# USB_CP2102.net
KiCad netlist of a schematic drawn in Altium Designer
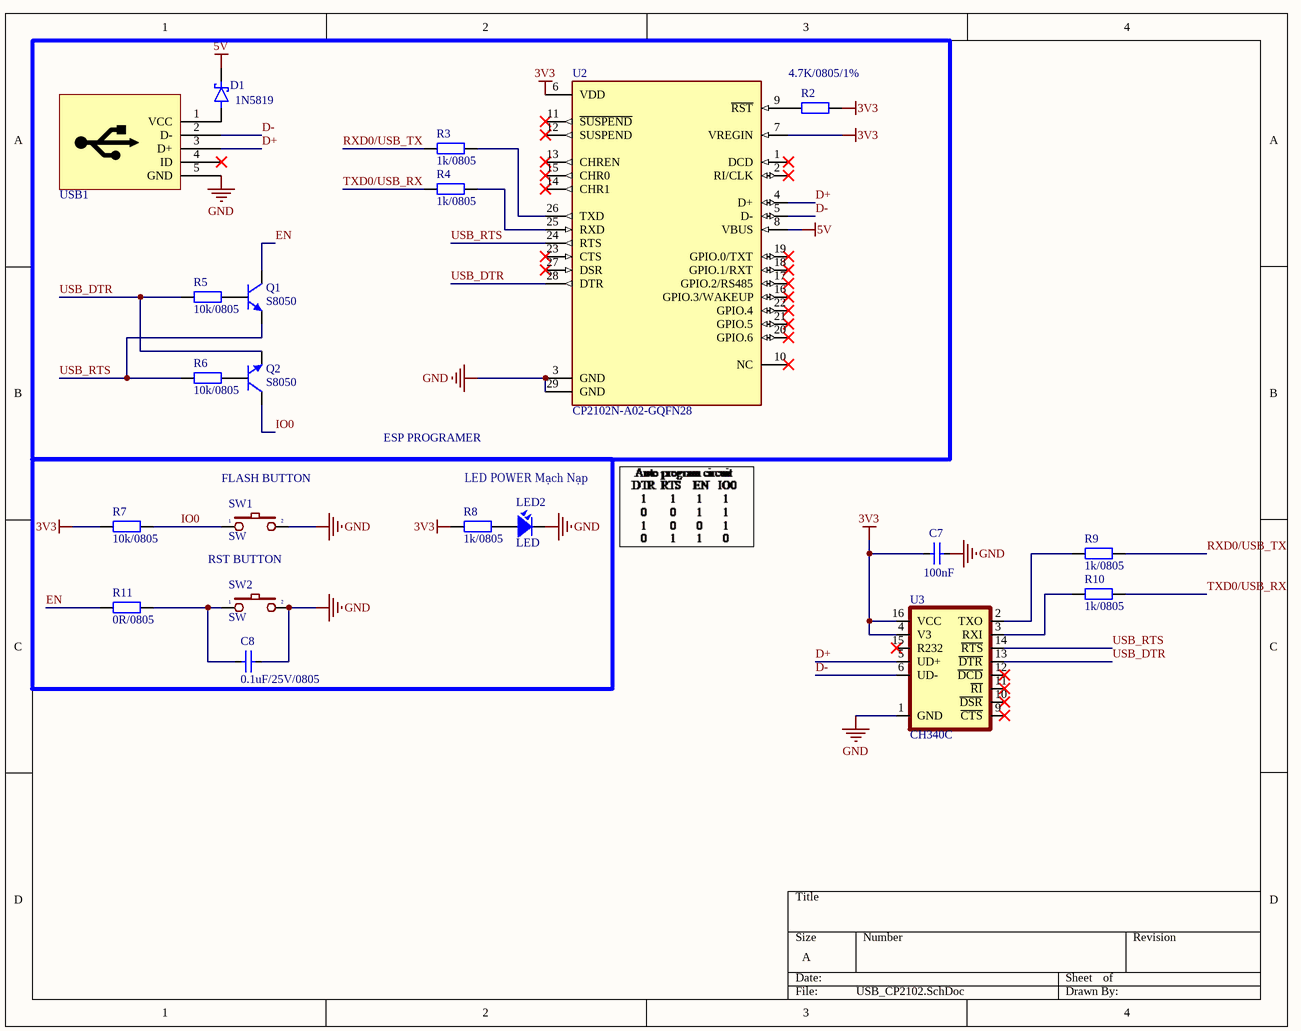
[diagram p0: USB_CP2102.SchDoc]

(export (version "E")
  (design (tool "Eeschema 10.0.6"))
  (components
    (comp (ref "C7")
      (value "100nF")
      (footprint "CAP_0402")
      (description "Capacitor")
      (fields (field (name "PUBLISHER") "Altium Limited"))
      (libsource (lib "My Library") (part "CapSMD"))
    )
    (comp (ref "C8")
      (value "0.1uF/25V/0805")
      (footprint "CAP_0805")
      (description "Capacitor")
      (fields (field (name "PUBLISHER") "Altium Limited"))
      (libsource (lib "My Library") (part "CapSMD"))
    )
    (comp (ref "D1")
      (value "1N5819")
      (footprint "SOD3715X145N")
      (description "Diode Schottky 40 V 1A Surface Mount SOD-123")
      (fields (field (name "MF") "Diodes Inc.") (field (name "MP") "1N5819HW-7-F"))
      (libsource (lib "1N5819HW-7-F") (part "1N5819HW-7-F"))
    )
    (comp (ref "LED2")
      (value "LED")
      (footprint "LED-0805-Green")
      (description "LED Single colour Green and Red")
      (libsource (lib "My Library") (part "LED"))
    )
    (comp (ref "Q1")
      (value "S8050")
      (footprint "SOT23")
      (description "NPN General")
      (fields (field (name "PUBLISHER") "Altium Limited"))
      (libsource (lib "My Library") (part "NPN"))
    )
    (comp (ref "Q2")
      (value "S8050")
      (footprint "SOT23")
      (description "NPN General")
      (fields (field (name "PUBLISHER") "Altium Limited"))
      (libsource (lib "My Library") (part "NPN"))
    )
    (comp (ref "R2")
      (value "4.7K/0805/1%")
      (footprint "RES-SMD-0805")
      (description "Resistor SMD")
      (fields
        (field (name "MANUFACTURER") "Generic Components")
        (field (name "PUBLISHER") "Altium Hobart Technology Centre")
      )
      (libsource (lib "My Library") (part "Resistor - SMD"))
    )
    (comp (ref "R3")
      (value "1k/0805")
      (footprint "RES-SMD-0805")
      (description "Resistor SMD")
      (fields
        (field (name "MANUFACTURER") "Generic Components")
        (field (name "PUBLISHER") "Altium Hobart Technology Centre")
      )
      (libsource (lib "My Library") (part "Resistor - SMD"))
    )
    (comp (ref "R4")
      (value "1k/0805")
      (footprint "RES-SMD-0805")
      (description "Resistor SMD")
      (fields
        (field (name "MANUFACTURER") "Generic Components")
        (field (name "PUBLISHER") "Altium Hobart Technology Centre")
      )
      (libsource (lib "My Library") (part "Resistor - SMD"))
    )
    (comp (ref "R5")
      (value "10k/0805")
      (footprint "RES-SMD-0805")
      (description "Resistor SMD")
      (fields
        (field (name "MANUFACTURER") "Generic Components")
        (field (name "PUBLISHER") "Altium Hobart Technology Centre")
      )
      (libsource (lib "My Library") (part "Resistor - SMD"))
    )
    (comp (ref "R6")
      (value "10k/0805")
      (footprint "RES-SMD-0805")
      (description "Resistor SMD")
      (fields
        (field (name "MANUFACTURER") "Generic Components")
        (field (name "PUBLISHER") "Altium Hobart Technology Centre")
      )
      (libsource (lib "My Library") (part "Resistor - SMD"))
    )
    (comp (ref "R7")
      (value "10k/0805")
      (footprint "RES-SMD-0805")
      (description "Resistor SMD")
      (fields
        (field (name "MANUFACTURER") "Generic Components")
        (field (name "PUBLISHER") "Altium Hobart Technology Centre")
      )
      (libsource (lib "My Library") (part "Resistor - SMD"))
    )
    (comp (ref "R8")
      (value "1k/0805")
      (footprint "RES-SMD-0805")
      (description "Resistor SMD")
      (fields
        (field (name "MANUFACTURER") "Generic Components")
        (field (name "PUBLISHER") "Altium Hobart Technology Centre")
      )
      (libsource (lib "My Library") (part "Resistor - SMD"))
    )
    (comp (ref "R9")
      (value "1k/0805")
      (footprint "RES-SMD-0805")
      (description "Resistor SMD")
      (fields
        (field (name "MANUFACTURER") "Generic Components")
        (field (name "PUBLISHER") "Altium Hobart Technology Centre")
      )
      (libsource (lib "My Library") (part "Resistor - SMD"))
    )
    (comp (ref "R10")
      (value "1k/0805")
      (footprint "RES-SMD-0805")
      (description "Resistor SMD")
      (fields
        (field (name "MANUFACTURER") "Generic Components")
        (field (name "PUBLISHER") "Altium Hobart Technology Centre")
      )
      (libsource (lib "My Library") (part "Resistor - SMD"))
    )
    (comp (ref "R11")
      (value "0R/0805")
      (footprint "RES-SMD-0805")
      (description "Resistor SMD")
      (fields
        (field (name "MANUFACTURER") "Generic Components")
        (field (name "PUBLISHER") "Altium Hobart Technology Centre")
      )
      (libsource (lib "My Library") (part "Resistor - SMD"))
    )
    (comp (ref "SW1")
      (value "SW")
      (footprint "SW-SMD")
      (description "Switch button 2 pin")
      (libsource (lib "My Library") (part "SW2"))
    )
    (comp (ref "SW2")
      (value "SW")
      (footprint "SW-SMD")
      (description "Switch button 2 pin")
      (libsource (lib "My Library") (part "SW2"))
    )
    (comp (ref "U2")
      (value "CP2102N-A02-GQFN28")
      (footprint "QFN50P500X500X80-29N")
      (description "USB Bridge, USB to UART USB 2.0 UART Interface 28-QFN (5x5)")
      (fields (field (name "MF") "Silicon Labs"))
      (libsource (lib "CP2102N-A02-GQFN28") (part "CP2102N-A02-GQFN28"))
    )
    (comp (ref "U3")
      (value "CH340C")
      (footprint "SOP-16")
      (description "USB to serial chip CH340")
      (fields (field (name "MF") "WCH"))
      (libsource (lib "My Library") (part "CH340C"))
    )
    (comp (ref "USB1")
      (value "USB")
      (footprint "HRS_ZX62D-B-5P8")
      (libsource (lib "My Library") (part "USB-M"))
    )
  )
  (nets
    (net (code "1") (name "/D+") (class "Default")
      (node (ref "U2") (pin "4") (pinfunction "D+_4") (pintype "bidirectional"))
      (node (ref "U3") (pin "5") (pinfunction "UD+_5") (pintype "bidirectional"))
      (node (ref "USB1") (pin "3") (pinfunction "D+_3") (pintype "passive"))
    )
    (net (code "2") (name "/D-") (class "Default")
      (node (ref "U2") (pin "5") (pinfunction "D-_5") (pintype "bidirectional"))
      (node (ref "U3") (pin "6") (pinfunction "UD-_6") (pintype "bidirectional"))
      (node (ref "USB1") (pin "2") (pinfunction "D-_2") (pintype "passive"))
    )
    (net (code "3") (name "/EN") (class "Default")
      (node (ref "Q1") (pin "2") (pinfunction "C_2") (pintype "passive"))
      (node (ref "R11") (pin "2") (pinfunction "2_2") (pintype "passive"))
    )
    (net (code "4") (name "/IO0") (class "Default")
      (node (ref "Q2") (pin "2") (pinfunction "C_2") (pintype "passive"))
      (node (ref "R7") (pin "1") (pinfunction "1_1") (pintype "passive"))
      (node (ref "SW1") (pin "1") (pinfunction "1_1") (pintype "passive"))
    )
    (net (code "5") (name "/RXD0{slash}USB_TX") (class "Default")
      (node (ref "R3") (pin "2") (pinfunction "2_2") (pintype "passive"))
      (node (ref "R9") (pin "2") (pinfunction "2_2") (pintype "passive"))
    )
    (net (code "6") (name "/TXD0{slash}USB_RX") (class "Default")
      (node (ref "R10") (pin "2") (pinfunction "2_2") (pintype "passive"))
      (node (ref "R4") (pin "2") (pinfunction "2_2") (pintype "passive"))
    )
    (net (code "7") (name "/USB_DTR") (class "Default")
      (node (ref "Q2") (pin "1") (pinfunction "E_1") (pintype "passive"))
      (node (ref "R5") (pin "2") (pinfunction "2_2") (pintype "passive"))
      (node (ref "U2") (pin "28") (pinfunction "DTR_28") (pintype "output"))
      (node (ref "U3") (pin "13") (pinfunction "~{DTR}_13") (pintype "bidirectional"))
    )
    (net (code "8") (name "/USB_RTS") (class "Default")
      (node (ref "Q1") (pin "1") (pinfunction "E_1") (pintype "passive"))
      (node (ref "R6") (pin "2") (pinfunction "2_2") (pintype "passive"))
      (node (ref "U2") (pin "24") (pinfunction "RTS_24") (pintype "output"))
      (node (ref "U3") (pin "14") (pinfunction "~{RTS}_14") (pintype "bidirectional"))
    )
    (net (code "9") (name "3V3") (class "Default")
      (node (ref "C7") (pin "1") (pinfunction "1_1") (pintype "passive"))
      (node (ref "R2") (pin "1") (pinfunction "1_1") (pintype "passive"))
      (node (ref "R7") (pin "2") (pinfunction "2_2") (pintype "passive"))
      (node (ref "R8") (pin "2") (pinfunction "2_2") (pintype "passive"))
      (node (ref "U2") (pin "6") (pinfunction "VDD_6") (pintype "power_in"))
      (node (ref "U2") (pin "7") (pinfunction "VREGIN_7") (pintype "input"))
      (node (ref "U3") (pin "16") (pinfunction "VCC_16") (pintype "bidirectional"))
      (node (ref "U3") (pin "4") (pinfunction "V3_4") (pintype "bidirectional"))
    )
    (net (code "10") (name "5V") (class "Default")
      (node (ref "D1") (pin "C") (pinfunction "K_C") (pintype "passive"))
      (node (ref "U2") (pin "8") (pinfunction "VBUS_8") (pintype "input"))
    )
    (net (code "11") (name "GND") (class "Default")
      (node (ref "C7") (pin "2") (pinfunction "2_2") (pintype "passive"))
      (node (ref "C8") (pin "2") (pinfunction "2_2") (pintype "passive"))
      (node (ref "LED2") (pin "2") (pinfunction "2_2") (pintype "passive"))
      (node (ref "SW1") (pin "2") (pinfunction "2_2") (pintype "passive"))
      (node (ref "SW2") (pin "2") (pinfunction "2_2") (pintype "passive"))
      (node (ref "U2") (pin "29") (pinfunction "GND_29") (pintype "power_in"))
      (node (ref "U2") (pin "3") (pinfunction "GND_3") (pintype "power_in"))
      (node (ref "U3") (pin "1") (pinfunction "GND_1") (pintype "bidirectional"))
      (node (ref "USB1") (pin "5") (pinfunction "GND_5") (pintype "passive"))
    )
    (net (code "12") (name "Net-(C8-Pad1)") (class "Default")
      (node (ref "C8") (pin "1") (pinfunction "1_1") (pintype "passive"))
      (node (ref "R11") (pin "1") (pinfunction "1_1") (pintype "passive"))
      (node (ref "SW2") (pin "1") (pinfunction "1_1") (pintype "passive"))
    )
    (net (code "13") (name "Net-(LED2-Pad1)") (class "Default")
      (node (ref "LED2") (pin "1") (pinfunction "1_1") (pintype "passive"))
      (node (ref "R8") (pin "1") (pinfunction "1_1") (pintype "passive"))
    )
    (net (code "14") (name "Net-(Q1-B)") (class "Default")
      (node (ref "Q1") (pin "3") (pinfunction "B_3") (pintype "passive"))
      (node (ref "R5") (pin "1") (pinfunction "1_1") (pintype "passive"))
    )
    (net (code "15") (name "Net-(Q2-B)") (class "Default")
      (node (ref "Q2") (pin "3") (pinfunction "B_3") (pintype "passive"))
      (node (ref "R6") (pin "1") (pinfunction "1_1") (pintype "passive"))
    )
    (net (code "16") (name "Net-(U2-RXD)") (class "Default")
      (node (ref "R4") (pin "1") (pinfunction "1_1") (pintype "passive"))
      (node (ref "U2") (pin "25") (pinfunction "RXD_25") (pintype "input"))
    )
    (net (code "17") (name "Net-(U2-TXD)") (class "Default")
      (node (ref "R3") (pin "1") (pinfunction "1_1") (pintype "passive"))
      (node (ref "U2") (pin "26") (pinfunction "TXD_26") (pintype "output"))
    )
    (net (code "18") (name "Net-(U2-~{RST})") (class "Default")
      (node (ref "R2") (pin "2") (pinfunction "2_2") (pintype "passive"))
      (node (ref "U2") (pin "9") (pinfunction "~{RST}_9") (pintype "input"))
    )
    (net (code "19") (name "Net-(U3-RXI)") (class "Default")
      (node (ref "R10") (pin "1") (pinfunction "1_1") (pintype "passive"))
      (node (ref "U3") (pin "3") (pinfunction "RXI_3") (pintype "bidirectional"))
    )
    (net (code "20") (name "Net-(U3-TXO)") (class "Default")
      (node (ref "R9") (pin "1") (pinfunction "1_1") (pintype "passive"))
      (node (ref "U3") (pin "2") (pinfunction "TXO_2") (pintype "bidirectional"))
    )
    (net (code "21") (name "Net-(USB1-VCC)") (class "Default")
      (node (ref "D1") (pin "A") (pinfunction "A_A") (pintype "passive"))
      (node (ref "USB1") (pin "1") (pinfunction "VCC_1") (pintype "passive"))
    )
    (net (code "22") (name "unconnected-(U2-CHR0-Pad15)") (class "Default")
      (node (ref "U2") (pin "15") (pinfunction "CHR0_15") (pintype "output+no_connect"))
    )
    (net (code "23") (name "unconnected-(U2-CHR1-Pad14)") (class "Default")
      (node (ref "U2") (pin "14") (pinfunction "CHR1_14") (pintype "output+no_connect"))
    )
    (net (code "24") (name "unconnected-(U2-CHREN-Pad13)") (class "Default")
      (node (ref "U2") (pin "13") (pinfunction "CHREN_13") (pintype "output+no_connect"))
    )
    (net (code "25") (name "unconnected-(U2-CTS-Pad23)") (class "Default")
      (node (ref "U2") (pin "23") (pinfunction "CTS_23") (pintype "input+no_connect"))
    )
    (net (code "26") (name "unconnected-(U2-DCD-Pad1)") (class "Default")
      (node (ref "U2") (pin "1") (pinfunction "DCD_1") (pintype "input+no_connect"))
    )
    (net (code "27") (name "unconnected-(U2-DSR-Pad27)") (class "Default")
      (node (ref "U2") (pin "27") (pinfunction "DSR_27") (pintype "input+no_connect"))
    )
    (net (code "28") (name "unconnected-(U2-GPIO.0{slash}TXT-Pad19)") (class "Default")
      (node (ref "U2") (pin "19") (pinfunction "GPIO.0/TXT_19") (pintype "bidirectional+no_connect"))
    )
    (net (code "29") (name "unconnected-(U2-GPIO.1{slash}RXT-Pad18)") (class "Default")
      (node (ref "U2") (pin "18") (pinfunction "GPIO.1/RXT_18") (pintype "bidirectional+no_connect"))
    )
    (net (code "30") (name "unconnected-(U2-GPIO.2{slash}RS485-Pad17)") (class "Default")
      (node (ref "U2") (pin "17") (pinfunction "GPIO.2/RS485_17") (pintype "bidirectional+no_connect"))
    )
    (net (code "31") (name "unconnected-(U2-GPIO.3{slash}WAKEUP-Pad16)") (class "Default")
      (node (ref "U2") (pin "16") (pinfunction "GPIO.3/WAKEUP_16") (pintype "bidirectional+no_connect"))
    )
    (net (code "32") (name "unconnected-(U2-GPIO.4-Pad22)") (class "Default")
      (node (ref "U2") (pin "22") (pinfunction "GPIO.4_22") (pintype "bidirectional+no_connect"))
    )
    (net (code "33") (name "unconnected-(U2-GPIO.5-Pad21)") (class "Default")
      (node (ref "U2") (pin "21") (pinfunction "GPIO.5_21") (pintype "bidirectional+no_connect"))
    )
    (net (code "34") (name "unconnected-(U2-GPIO.6-Pad20)") (class "Default")
      (node (ref "U2") (pin "20") (pinfunction "GPIO.6_20") (pintype "bidirectional+no_connect"))
    )
    (net (code "35") (name "unconnected-(U2-NC-Pad10)") (class "Default")
      (node (ref "U2") (pin "10") (pinfunction "NC_10") (pintype "passive+no_connect"))
    )
    (net (code "36") (name "unconnected-(U2-RI{slash}CLK-Pad2)") (class "Default")
      (node (ref "U2") (pin "2") (pinfunction "RI/CLK_2") (pintype "bidirectional+no_connect"))
    )
    (net (code "37") (name "unconnected-(U2-SUSPEND-Pad12)") (class "Default")
      (node (ref "U2") (pin "12") (pinfunction "SUSPEND_12") (pintype "output+no_connect"))
    )
    (net (code "38") (name "unconnected-(U2-~{SUSPEND}-Pad11)") (class "Default")
      (node (ref "U2") (pin "11") (pinfunction "~{SUSPEND}_11") (pintype "output+no_connect"))
    )
    (net (code "39") (name "unconnected-(U3-R232-Pad15)") (class "Default")
      (node (ref "U3") (pin "15") (pinfunction "R232_15") (pintype "bidirectional+no_connect"))
    )
    (net (code "40") (name "unconnected-(U3-~{CTS}-Pad9)") (class "Default")
      (node (ref "U3") (pin "9") (pinfunction "~{CTS}_9") (pintype "bidirectional+no_connect"))
    )
    (net (code "41") (name "unconnected-(U3-~{DCD}-Pad12)") (class "Default")
      (node (ref "U3") (pin "12") (pinfunction "~{DCD}_12") (pintype "bidirectional+no_connect"))
    )
    (net (code "42") (name "unconnected-(U3-~{DSR}-Pad10)") (class "Default")
      (node (ref "U3") (pin "10") (pinfunction "~{DSR}_10") (pintype "bidirectional+no_connect"))
    )
    (net (code "43") (name "unconnected-(U3-~{RI}-Pad11)") (class "Default")
      (node (ref "U3") (pin "11") (pinfunction "~{RI}_11") (pintype "bidirectional+no_connect"))
    )
    (net (code "44") (name "unconnected-(USB1-ID-Pad4)") (class "Default")
      (node (ref "USB1") (pin "4") (pinfunction "ID_4") (pintype "passive+no_connect"))
    )
  )
)
